# 555_timer.net
KiCad netlist of a schematic drawn in Altium Designer
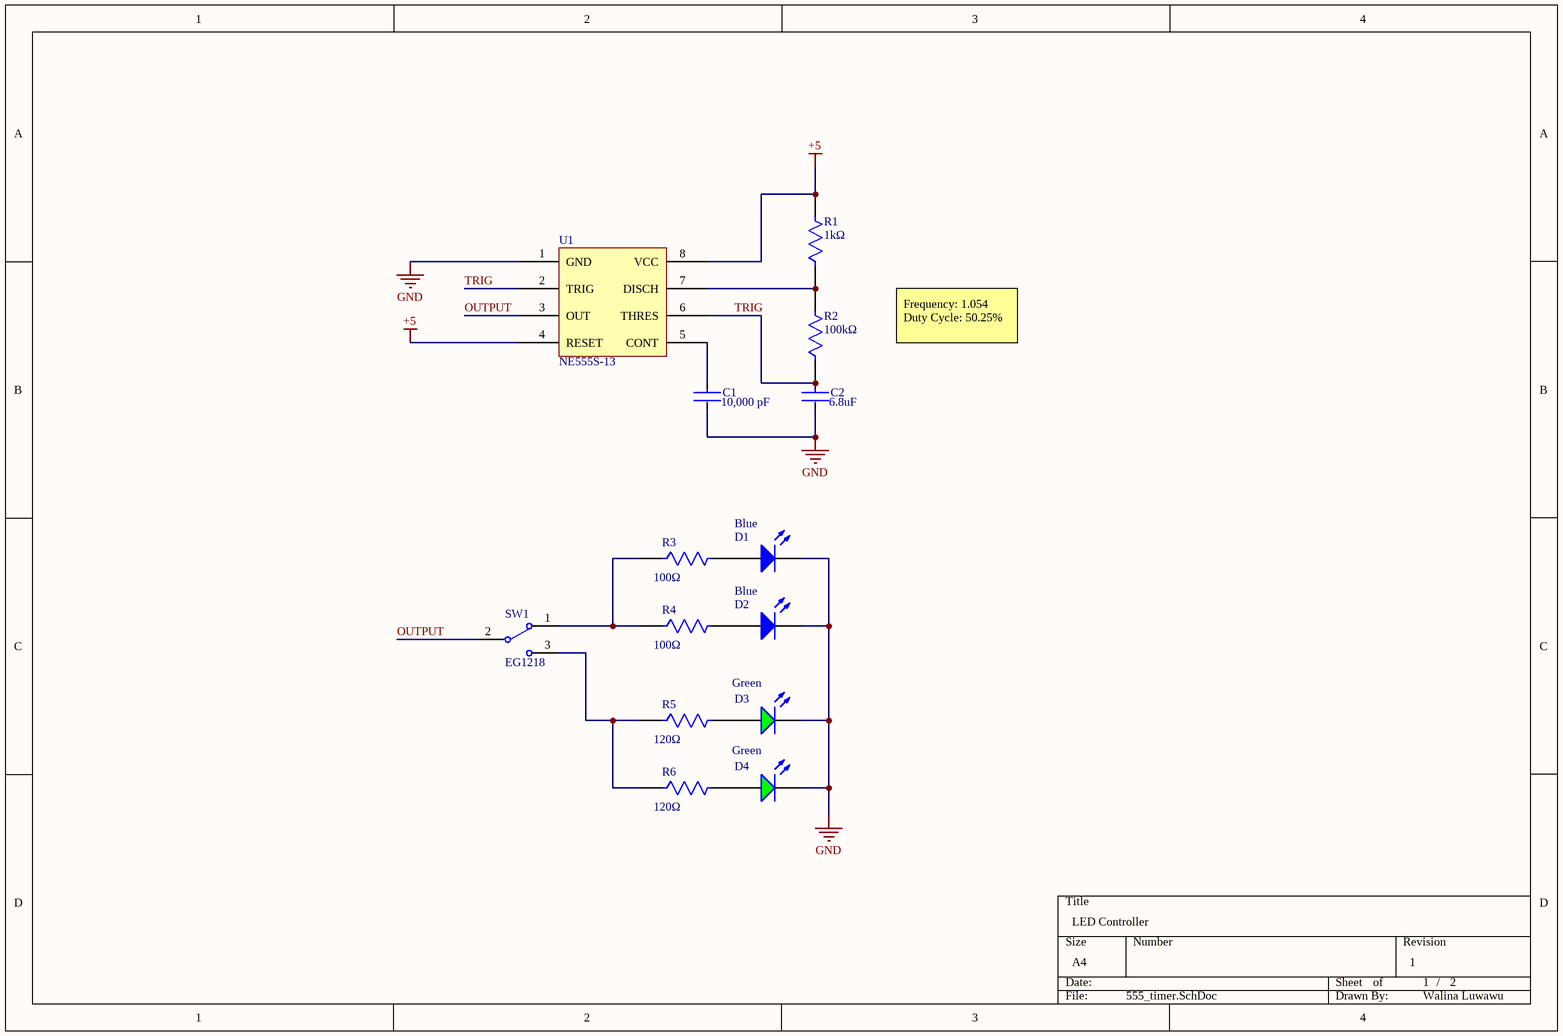
[diagram p0: 555_timer.SchDoc]

(export (version "E")
  (design (tool "Eeschema 10.0.6"))
  (components
    (comp (ref "C1")
      (value "C1206C103K5RAC7210")
      (footprint "FP-C1206C-EB-MFG")
      (description "C1206 10,000 pF X7R 10.00% 50 V")
      (fields (field (name "TOLERANCE") "0.1") (field (name "CAPACITANCE") "10,000 pF"))
      (libsource (lib "Altium Content Vault") (part "b4654b650e69147ec39a6b967a45e02"))
    )
    (comp (ref "C2")
      (value "CGA4J3X7S1A685K125AB")
      (footprint "FP-CGA4J-IPC_B")
      (description "Cap Ceramic 6.8uF 10V X7S 10% Pad SMD 0805 +125°C Automotive T/R")
      (fields (field (name "TOLERANCE") "10%") (field (name "CAPACITANCE") "6.8uF"))
      (libsource (lib "Altium Content Vault") (part "b4654b650e69147ec39a6b967a45e02"))
    )
    (comp (ref "D1")
      (value "151051BS04000")
      (footprint "WL-TMRC_D5.9H8.7")
      (description "Single Color LED, Blue, Diffused, T-1 3/4, 4.9mm")
      (fields (field (name "COLOR") "Blue"))
      (libsource (lib "Altium Content Vault") (part "LED_Blue_1A-2K"))
    )
    (comp (ref "D2")
      (value "151051BS04000")
      (footprint "WL-TMRC_D5.9H8.7")
      (description "Single Color LED, Blue, Diffused, T-1 3/4, 4.9mm")
      (fields (field (name "COLOR") "Blue"))
      (libsource (lib "Altium Content Vault") (part "LED_Blue_1A-2K"))
    )
    (comp (ref "D3")
      (value "151031VS06000")
      (footprint "WL-TMRC_D3.95H5.3")
      (description "Led, Green, T-1 (3Mm), 568 Nm, 2.2 V, 30 Ma, 20 Mcd Rohs Compliant: Yes")
      (fields (field (name "COLOR") "Green"))
      (libsource (lib "Altium Content Vault") (part "LED_Green_1A-2K"))
    )
    (comp (ref "D4")
      (value "151031VS06000")
      (footprint "WL-TMRC_D3.95H5.3")
      (description "Led, Green, T-1 (3Mm), 568 Nm, 2.2 V, 30 Ma, 20 Mcd Rohs Compliant: Yes")
      (fields (field (name "COLOR") "Green"))
      (libsource (lib "Altium Content Vault") (part "LED_Green_1A-2K"))
    )
    (comp (ref "R1")
      (value "RK73H2ATTE1001F")
      (footprint "FP-RK73H2A-MFG")
      (description "1kΩ ±1% 0.25W Chip Resistor 0805 Thick Film AEC-Q200 Qualified")
      (fields (field (name "RESISTANCE") "1kΩ") (field (name "TOLERANCE") "1%"))
      (libsource (lib "Altium Content Vault") (part "1029c3af85768c4190bb7ad29bc67b5"))
    )
    (comp (ref "R2")
      (value "RR0816P-104-D")
      (footprint "FP-RR0816-IPC_A")
      (description "100kΩ ±0.5% 0.0625W 1/16W Chip Resistor 0603 (1608 Metric) Thin Film")
      (fields (field (name "RESISTANCE") "100kΩ") (field (name "TOLERANCE") "0.5%"))
      (libsource (lib "Altium Content Vault") (part "1029c3af85768c4190bb7ad29bc67b5"))
    )
    (comp (ref "R3")
      (value "CR0805-JW-101ELF")
      (footprint "FP-CR0805-IPC_B")
      (description "Thick Film Chip Resistors 0805 100Ω 0.125W 5% 200ppm/°C")
      (fields (field (name "TOLERANCE") "5%") (field (name "RESISTANCE") "100Ω"))
      (libsource (lib "Altium Content Vault") (part "1029c3af85768c4190bb7ad29bc67b5"))
    )
    (comp (ref "R4")
      (value "CR0805-JW-101ELF")
      (footprint "FP-CR0805-IPC_B")
      (description "Thick Film Chip Resistors 0805 100Ω 0.125W 5% 200ppm/°C")
      (fields (field (name "TOLERANCE") "5%") (field (name "RESISTANCE") "100Ω"))
      (libsource (lib "Altium Content Vault") (part "1029c3af85768c4190bb7ad29bc67b5"))
    )
    (comp (ref "R5")
      (value "CRGCQ0805F120R")
      (footprint "FP-CRGCQ0805-IPC_C")
      (description "CRGCQ 0805 120R 1%")
      (fields
        (field (name "OCTOPART") "https://octopart.com/crgcq0805f120r-te+connectivity-91018143")
        (field (name "TOLERANCE") "0.01")
        (field (name "RESISTANCE") "120Ω")
      )
      (libsource (lib "Altium Content Vault") (part "1029c3af85768c4190bb7ad29bc67b5"))
    )
    (comp (ref "R6")
      (value "CRGCQ0805F120R")
      (footprint "FP-CRGCQ0805-IPC_C")
      (description "CRGCQ 0805 120R 1%")
      (fields
        (field (name "OCTOPART") "https://octopart.com/crgcq0805f120r-te+connectivity-91018143")
        (field (name "TOLERANCE") "0.01")
        (field (name "RESISTANCE") "120Ω")
      )
      (libsource (lib "Altium Content Vault") (part "1029c3af85768c4190bb7ad29bc67b5"))
    )
    (comp (ref "SW1")
      (value "EG1218")
      (footprint "ESWI-EG1218_V")
      (description "Slide Switch, 500 V, -20 to 70 degC, 3-Pin THD, RoHS")
      (libsource (lib "Altium Content Vault") (part "SW-SPDT-3_B"))
    )
    (comp (ref "U1")
      (value "NE555S-13")
      (footprint "NE555S-13")
      (description "IC OSC SNGL TIMER 500KHZ 8-SOIC")
      (libsource (lib "TutorialLibrary") (part "NE555S-13"))
    )
  )
  (nets
    (net (code "1") (name "+5") (class "Default")
      (node (ref "R1") (pin "2") (pinfunction "2_2") (pintype "passive"))
      (node (ref "U1") (pin "4") (pinfunction "RESET_4") (pintype "passive"))
      (node (ref "U1") (pin "8") (pinfunction "VCC_8") (pintype "passive"))
    )
    (net (code "2") (name "/OUTPUT") (class "Default")
      (node (ref "SW1") (pin "2") (pinfunction "COM_2") (pintype "passive"))
      (node (ref "U1") (pin "3") (pinfunction "OUT_3") (pintype "passive"))
    )
    (net (code "3") (name "/TRIG") (class "Default")
      (node (ref "C2") (pin "1") (pinfunction "1_1") (pintype "passive"))
      (node (ref "R2") (pin "1") (pinfunction "1_1") (pintype "passive"))
      (node (ref "U1") (pin "2") (pinfunction "TRIG_2") (pintype "passive"))
      (node (ref "U1") (pin "6") (pinfunction "THRES_6") (pintype "passive"))
    )
    (net (code "4") (name "GND") (class "Default")
      (node (ref "C1") (pin "2") (pinfunction "2_2") (pintype "passive"))
      (node (ref "C2") (pin "2") (pinfunction "2_2") (pintype "passive"))
      (node (ref "D1") (pin "2") (pinfunction "K_2") (pintype "passive"))
      (node (ref "D2") (pin "2") (pinfunction "K_2") (pintype "passive"))
      (node (ref "D3") (pin "2") (pinfunction "K_2") (pintype "passive"))
      (node (ref "D4") (pin "2") (pinfunction "K_2") (pintype "passive"))
      (node (ref "U1") (pin "1") (pinfunction "GND_1") (pintype "passive"))
    )
    (net (code "5") (name "Net-(D1-A)") (class "Default")
      (node (ref "D1") (pin "1") (pinfunction "A_1") (pintype "passive"))
      (node (ref "R3") (pin "2") (pinfunction "2_2") (pintype "passive"))
    )
    (net (code "6") (name "Net-(D2-A)") (class "Default")
      (node (ref "D2") (pin "1") (pinfunction "A_1") (pintype "passive"))
      (node (ref "R4") (pin "2") (pinfunction "2_2") (pintype "passive"))
    )
    (net (code "7") (name "Net-(D3-A)") (class "Default")
      (node (ref "D3") (pin "1") (pinfunction "A_1") (pintype "passive"))
      (node (ref "R5") (pin "2") (pinfunction "2_2") (pintype "passive"))
    )
    (net (code "8") (name "Net-(D4-A)") (class "Default")
      (node (ref "D4") (pin "1") (pinfunction "A_1") (pintype "passive"))
      (node (ref "R6") (pin "2") (pinfunction "2_2") (pintype "passive"))
    )
    (net (code "9") (name "Net-(R3-Pad1)") (class "Default")
      (node (ref "R3") (pin "1") (pinfunction "1_1") (pintype "passive"))
      (node (ref "R4") (pin "1") (pinfunction "1_1") (pintype "passive"))
      (node (ref "SW1") (pin "1") (pinfunction "1_1") (pintype "passive"))
    )
    (net (code "10") (name "Net-(R5-Pad1)") (class "Default")
      (node (ref "R5") (pin "1") (pinfunction "1_1") (pintype "passive"))
      (node (ref "R6") (pin "1") (pinfunction "1_1") (pintype "passive"))
      (node (ref "SW1") (pin "3") (pinfunction "3_3") (pintype "passive"))
    )
    (net (code "11") (name "Net-(U1-CONT)") (class "Default")
      (node (ref "C1") (pin "1") (pinfunction "1_1") (pintype "passive"))
      (node (ref "U1") (pin "5") (pinfunction "CONT_5") (pintype "passive"))
    )
    (net (code "12") (name "Net-(U1-DISCH)") (class "Default")
      (node (ref "R1") (pin "1") (pinfunction "1_1") (pintype "passive"))
      (node (ref "R2") (pin "2") (pinfunction "2_2") (pintype "passive"))
      (node (ref "U1") (pin "7") (pinfunction "DISCH_7") (pintype "passive"))
    )
  )
)
